# projek_robot_1_fix.net
KiCad netlist of a schematic drawn in EAGLE
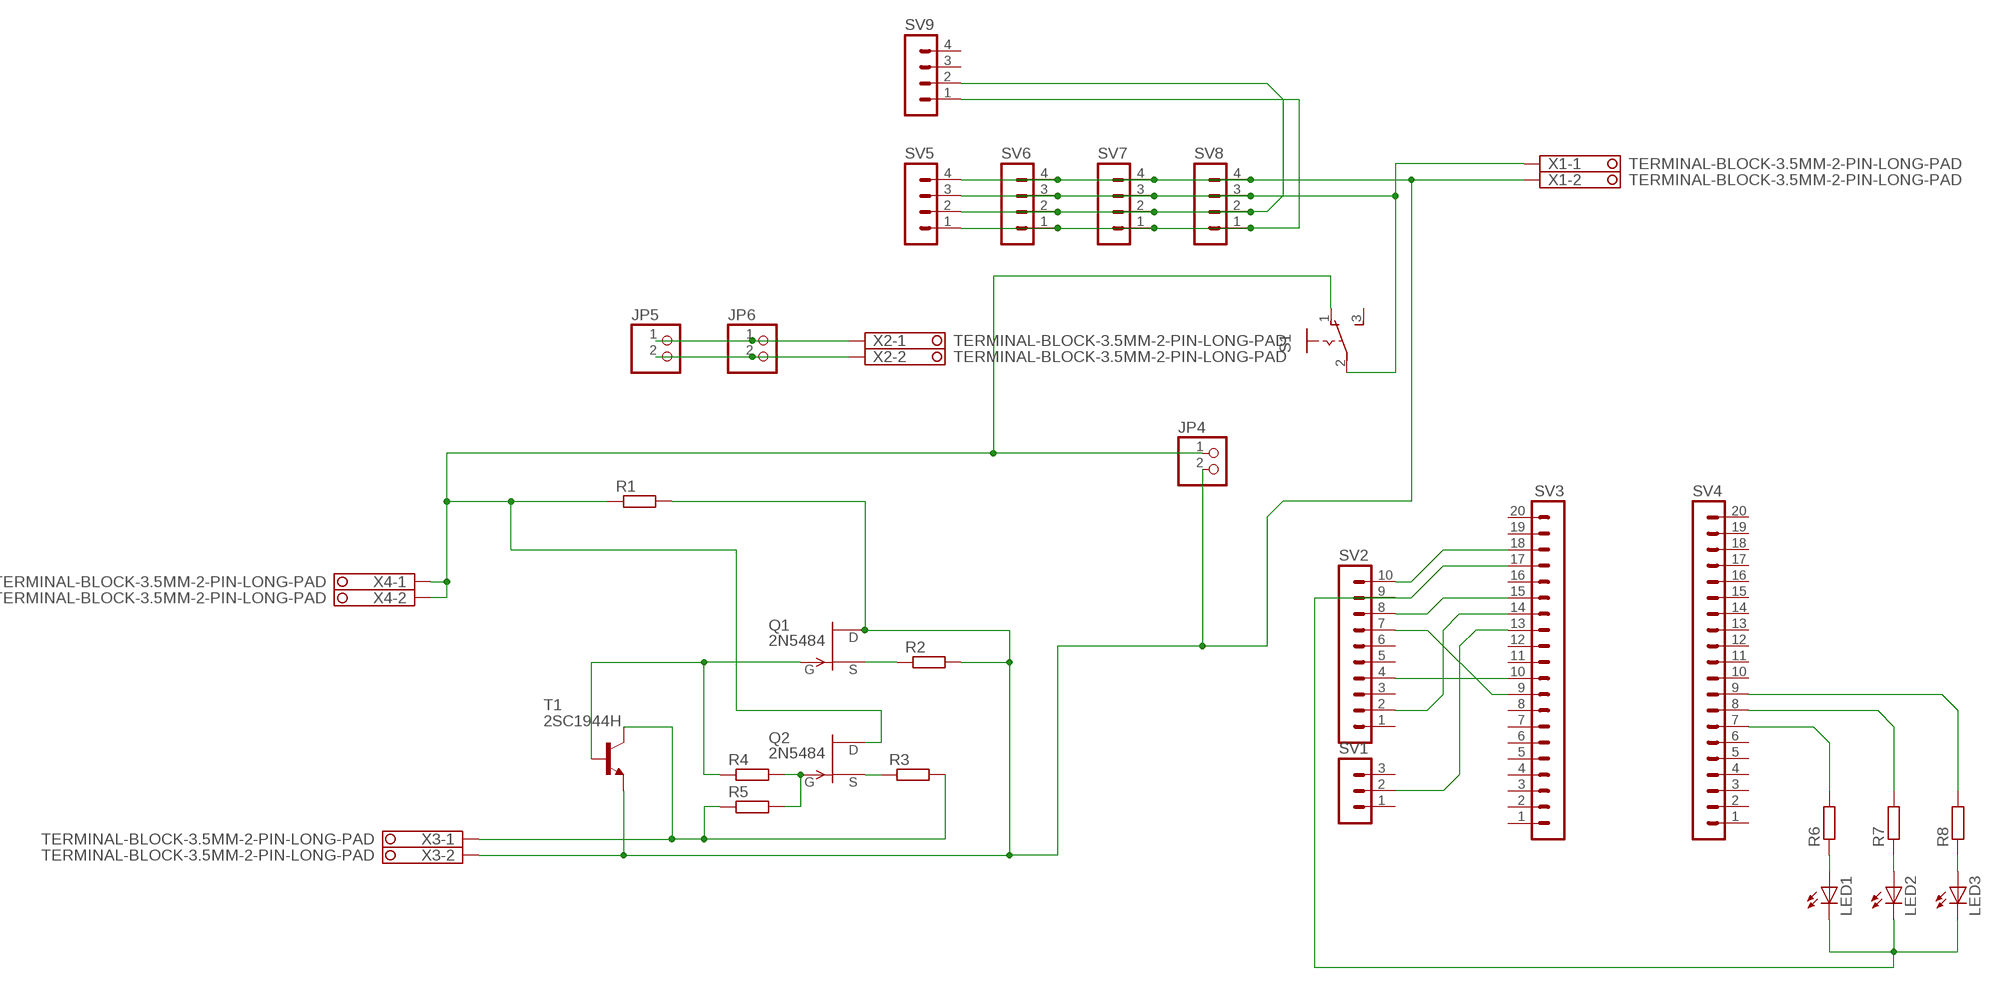
[diagram p0: schematic, sheet 1]

(export (version "E")
  (design (tool "Eeschema 10.0.6"))
  (components
    (comp (ref "JP4")
      (value "PINHD-1X2")
      (footprint "eagle-import:1X02")
      (libsource (lib "eagle-import") (part "PINHD-1X2"))
    )
    (comp (ref "JP5")
      (value "PINHD-1X2")
      (footprint "eagle-import:1X02")
      (libsource (lib "eagle-import") (part "PINHD-1X2"))
    )
    (comp (ref "JP6")
      (value "PINHD-1X2")
      (footprint "eagle-import:1X02")
      (libsource (lib "eagle-import") (part "PINHD-1X2"))
    )
    (comp (ref "LED1")
      (value "LED5MM")
      (footprint "eagle-import:LED5MM")
      (libsource (lib "eagle-import") (part "LED5MM"))
    )
    (comp (ref "LED2")
      (value "LED5MM")
      (footprint "eagle-import:LED5MM")
      (libsource (lib "eagle-import") (part "LED5MM"))
    )
    (comp (ref "LED3")
      (value "LED5MM")
      (footprint "eagle-import:LED5MM")
      (libsource (lib "eagle-import") (part "LED5MM"))
    )
    (comp (ref "Q1")
      (value "2N5484")
      (footprint "eagle-import:TO92-")
      (libsource (lib "eagle-import") (part "?5482N4"))
    )
    (comp (ref "Q2")
      (value "2N5484")
      (footprint "eagle-import:TO92-")
      (libsource (lib "eagle-import") (part "?5482N4"))
    )
    (comp (ref "R1")
      (value "R-EU_0207/7")
      (footprint "eagle-import:0207_7")
      (libsource (lib "eagle-import") (part "R-EU_0207/7"))
    )
    (comp (ref "R2")
      (value "R-EU_0207/7")
      (footprint "eagle-import:0207_7")
      (libsource (lib "eagle-import") (part "R-EU_0207/7"))
    )
    (comp (ref "R3")
      (value "R-EU_0207/7")
      (footprint "eagle-import:0207_7")
      (libsource (lib "eagle-import") (part "R-EU_0207/7"))
    )
    (comp (ref "R4")
      (value "R-EU_0207/7")
      (footprint "eagle-import:0207_7")
      (libsource (lib "eagle-import") (part "R-EU_0207/7"))
    )
    (comp (ref "R5")
      (value "R-EU_0207/7")
      (footprint "eagle-import:0207_7")
      (libsource (lib "eagle-import") (part "R-EU_0207/7"))
    )
    (comp (ref "R6")
      (value "R-EU_0207/7")
      (footprint "eagle-import:0207_7")
      (libsource (lib "eagle-import") (part "R-EU_0207/7"))
    )
    (comp (ref "R7")
      (value "R-EU_0207/7")
      (footprint "eagle-import:0207_7")
      (libsource (lib "eagle-import") (part "R-EU_0207/7"))
    )
    (comp (ref "R8")
      (value "R-EU_0207/7")
      (footprint "eagle-import:0207_7")
      (libsource (lib "eagle-import") (part "R-EU_0207/7"))
    )
    (comp (ref "S1")
      (value "M251")
      (footprint "eagle-import:M251")
      (libsource (lib "eagle-import") (part "M251"))
    )
    (comp (ref "SV1")
      (value "MA03-1")
      (footprint "eagle-import:MA03-1")
      (libsource (lib "eagle-import") (part "MA03-1"))
    )
    (comp (ref "SV2")
      (value "MA10-1")
      (footprint "eagle-import:MA10-1")
      (libsource (lib "eagle-import") (part "MA10-1"))
    )
    (comp (ref "SV3")
      (value "MA20-1")
      (footprint "eagle-import:MA20-1")
      (libsource (lib "eagle-import") (part "MA20-1"))
    )
    (comp (ref "SV4")
      (value "MA20-1")
      (footprint "eagle-import:MA20-1")
      (libsource (lib "eagle-import") (part "MA20-1"))
    )
    (comp (ref "SV5")
      (value "MA04-1")
      (footprint "eagle-import:MA04-1")
      (libsource (lib "eagle-import") (part "MA04-1"))
    )
    (comp (ref "SV6")
      (value "MA04-1")
      (footprint "eagle-import:MA04-1")
      (libsource (lib "eagle-import") (part "MA04-1"))
    )
    (comp (ref "SV7")
      (value "MA04-1")
      (footprint "eagle-import:MA04-1")
      (libsource (lib "eagle-import") (part "MA04-1"))
    )
    (comp (ref "SV8")
      (value "MA04-1")
      (footprint "eagle-import:MA04-1")
      (libsource (lib "eagle-import") (part "MA04-1"))
    )
    (comp (ref "SV9")
      (value "MA04-1")
      (footprint "eagle-import:MA04-1")
      (libsource (lib "eagle-import") (part "MA04-1"))
    )
    (comp (ref "T1")
      (value "2SC1944H")
      (footprint "eagle-import:T-30")
      (libsource (lib "eagle-import") (part "2SC1944H"))
    )
    (comp (ref "X1")
      (value "TERMINAL-BLOCK-3.5MM-2-PIN-LONG-PAD")
      (footprint "eagle-import:TERMINAL-BLOCK-2-PIN-3.5MM-LONG-PAD")
      (libsource (lib "eagle-import") (part "TERMINAL-BLOCK-3.5MM-2-PIN-LONG-PAD"))
    )
    (comp (ref "X2")
      (value "TERMINAL-BLOCK-3.5MM-2-PIN-LONG-PAD")
      (footprint "eagle-import:TERMINAL-BLOCK-2-PIN-3.5MM-LONG-PAD")
      (libsource (lib "eagle-import") (part "TERMINAL-BLOCK-3.5MM-2-PIN-LONG-PAD"))
    )
    (comp (ref "X3")
      (value "TERMINAL-BLOCK-3.5MM-2-PIN-LONG-PAD")
      (footprint "eagle-import:TERMINAL-BLOCK-2-PIN-3.5MM-LONG-PAD")
      (libsource (lib "eagle-import") (part "TERMINAL-BLOCK-3.5MM-2-PIN-LONG-PAD"))
    )
    (comp (ref "X4")
      (value "TERMINAL-BLOCK-3.5MM-2-PIN-LONG-PAD")
      (footprint "eagle-import:TERMINAL-BLOCK-2-PIN-3.5MM-LONG-PAD")
      (libsource (lib "eagle-import") (part "TERMINAL-BLOCK-3.5MM-2-PIN-LONG-PAD"))
    )
  )
  (nets
    (net (code "1") (name "Net-(LED1-C)") (class "Default")
      (node (ref "LED1") (pin "K") (pinfunction "C_K") (pintype "passive"))
      (node (ref "LED2") (pin "K") (pinfunction "C_K") (pintype "passive"))
      (node (ref "LED3") (pin "K") (pinfunction "C_K") (pintype "passive"))
      (node (ref "SV2") (pin "9") (pinfunction "9_9") (pintype "passive"))
      (node (ref "SV3") (pin "17") (pinfunction "17_17") (pintype "passive"))
    )
    (net (code "2") (name "Net-(LED1-PadA)") (class "Default")
      (node (ref "LED1") (pin "A") (pinfunction "A_A") (pintype "passive"))
      (node (ref "R6") (pin "1") (pinfunction "1_1") (pintype "passive"))
    )
    (net (code "3") (name "Net-(LED2-PadA)") (class "Default")
      (node (ref "LED2") (pin "A") (pinfunction "A_A") (pintype "passive"))
      (node (ref "R7") (pin "1") (pinfunction "1_1") (pintype "passive"))
    )
    (net (code "4") (name "Net-(LED3-PadA)") (class "Default")
      (node (ref "LED3") (pin "A") (pinfunction "A_A") (pintype "passive"))
      (node (ref "R8") (pin "1") (pinfunction "1_1") (pintype "passive"))
    )
    (net (code "5") (name "Net-(Q1-D)") (class "Default")
      (node (ref "JP4") (pin "2") (pinfunction "2_2") (pintype "passive"))
      (node (ref "Q1") (pin "3") (pinfunction "D_3") (pintype "passive"))
      (node (ref "R1") (pin "2") (pinfunction "2_2") (pintype "passive"))
      (node (ref "R2") (pin "2") (pinfunction "2_2") (pintype "passive"))
      (node (ref "SV5") (pin "4") (pinfunction "4_4") (pintype "passive"))
      (node (ref "SV6") (pin "4") (pinfunction "4_4") (pintype "passive"))
      (node (ref "SV7") (pin "4") (pinfunction "4_4") (pintype "passive"))
      (node (ref "SV8") (pin "4") (pinfunction "4_4") (pintype "passive"))
      (node (ref "T1") (pin "3") (pinfunction "E_3") (pintype "passive"))
      (node (ref "X1") (pin "2") (pinfunction "K_2") (pintype "passive"))
      (node (ref "X3") (pin "2") (pinfunction "K_2") (pintype "passive"))
    )
    (net (code "6") (name "Net-(Q1-G)") (class "Default")
      (node (ref "Q1") (pin "1") (pinfunction "G_1") (pintype "passive"))
      (node (ref "R4") (pin "1") (pinfunction "1_1") (pintype "passive"))
      (node (ref "T1") (pin "1") (pinfunction "B_1") (pintype "passive"))
    )
    (net (code "7") (name "Net-(Q1-S)") (class "Default")
      (node (ref "Q1") (pin "2") (pinfunction "S_2") (pintype "passive"))
      (node (ref "R2") (pin "1") (pinfunction "1_1") (pintype "passive"))
    )
    (net (code "8") (name "Net-(Q2-D)") (class "Default")
      (node (ref "JP4") (pin "1") (pinfunction "1_1") (pintype "passive"))
      (node (ref "Q2") (pin "3") (pinfunction "D_3") (pintype "passive"))
      (node (ref "R1") (pin "1") (pinfunction "1_1") (pintype "passive"))
      (node (ref "S1") (pin "1") (pinfunction "O_1") (pintype "passive"))
      (node (ref "X4") (pin "1") (pinfunction "K_1") (pintype "passive"))
      (node (ref "X4") (pin "2") (pinfunction "K_2") (pintype "passive"))
    )
    (net (code "9") (name "Net-(Q2-G)") (class "Default")
      (node (ref "Q2") (pin "1") (pinfunction "G_1") (pintype "passive"))
      (node (ref "R4") (pin "2") (pinfunction "2_2") (pintype "passive"))
      (node (ref "R5") (pin "2") (pinfunction "2_2") (pintype "passive"))
    )
    (net (code "10") (name "Net-(Q2-S)") (class "Default")
      (node (ref "Q2") (pin "2") (pinfunction "S_2") (pintype "passive"))
      (node (ref "R3") (pin "1") (pinfunction "1_1") (pintype "passive"))
    )
    (net (code "11") (name "Net-(R6-Pad2)") (class "Default")
      (node (ref "R6") (pin "2") (pinfunction "2_2") (pintype "passive"))
      (node (ref "SV4") (pin "7") (pinfunction "7_7") (pintype "passive"))
    )
    (net (code "12") (name "Net-(R7-Pad2)") (class "Default")
      (node (ref "R7") (pin "2") (pinfunction "2_2") (pintype "passive"))
      (node (ref "SV4") (pin "8") (pinfunction "8_8") (pintype "passive"))
    )
    (net (code "13") (name "Net-(R8-Pad2)") (class "Default")
      (node (ref "R8") (pin "2") (pinfunction "2_2") (pintype "passive"))
      (node (ref "SV4") (pin "9") (pinfunction "9_9") (pintype "passive"))
    )
    (net (code "14") (name "Net-(S1-P)") (class "Default")
      (node (ref "S1") (pin "2") (pinfunction "P_2") (pintype "passive"))
      (node (ref "SV5") (pin "3") (pinfunction "3_3") (pintype "passive"))
      (node (ref "SV6") (pin "3") (pinfunction "3_3") (pintype "passive"))
      (node (ref "SV7") (pin "3") (pinfunction "3_3") (pintype "passive"))
      (node (ref "SV8") (pin "3") (pinfunction "3_3") (pintype "passive"))
      (node (ref "X1") (pin "1") (pinfunction "K_1") (pintype "passive"))
    )
    (net (code "15") (name "Net-(SV1-Pad2)") (class "Default")
      (node (ref "SV1") (pin "2") (pinfunction "2_2") (pintype "passive"))
      (node (ref "SV3") (pin "13") (pinfunction "13_13") (pintype "passive"))
    )
    (net (code "16") (name "Net-(SV2-Pad2)") (class "Default")
      (node (ref "SV2") (pin "2") (pinfunction "2_2") (pintype "passive"))
      (node (ref "SV3") (pin "14") (pinfunction "14_14") (pintype "passive"))
    )
    (net (code "17") (name "Net-(SV2-Pad4)") (class "Default")
      (node (ref "SV2") (pin "4") (pinfunction "4_4") (pintype "passive"))
      (node (ref "SV3") (pin "10") (pinfunction "10_10") (pintype "passive"))
    )
    (net (code "18") (name "Net-(SV2-Pad7)") (class "Default")
      (node (ref "SV2") (pin "7") (pinfunction "7_7") (pintype "passive"))
      (node (ref "SV3") (pin "9") (pinfunction "9_9") (pintype "passive"))
    )
    (net (code "19") (name "Net-(SV2-Pad8)") (class "Default")
      (node (ref "SV2") (pin "8") (pinfunction "8_8") (pintype "passive"))
      (node (ref "SV3") (pin "15") (pinfunction "15_15") (pintype "passive"))
    )
    (net (code "20") (name "Net-(SV2-Pad10)") (class "Default")
      (node (ref "SV2") (pin "10") (pinfunction "10_10") (pintype "passive"))
      (node (ref "SV3") (pin "18") (pinfunction "18_18") (pintype "passive"))
    )
    (net (code "21") (name "Net-(SV5-Pad1)") (class "Default")
      (node (ref "SV5") (pin "1") (pinfunction "1_1") (pintype "passive"))
      (node (ref "SV6") (pin "1") (pinfunction "1_1") (pintype "passive"))
      (node (ref "SV7") (pin "1") (pinfunction "1_1") (pintype "passive"))
      (node (ref "SV8") (pin "1") (pinfunction "1_1") (pintype "passive"))
      (node (ref "SV9") (pin "1") (pinfunction "1_1") (pintype "passive"))
    )
    (net (code "22") (name "Net-(SV5-Pad2)") (class "Default")
      (node (ref "SV5") (pin "2") (pinfunction "2_2") (pintype "passive"))
      (node (ref "SV6") (pin "2") (pinfunction "2_2") (pintype "passive"))
      (node (ref "SV7") (pin "2") (pinfunction "2_2") (pintype "passive"))
      (node (ref "SV8") (pin "2") (pinfunction "2_2") (pintype "passive"))
      (node (ref "SV9") (pin "2") (pinfunction "2_2") (pintype "passive"))
    )
    (net (code "23") (name "Net-(T1-C)") (class "Default")
      (node (ref "R3") (pin "2") (pinfunction "2_2") (pintype "passive"))
      (node (ref "R5") (pin "1") (pinfunction "1_1") (pintype "passive"))
      (node (ref "T1") (pin "2") (pinfunction "C_2") (pintype "passive"))
      (node (ref "X3") (pin "1") (pinfunction "K_1") (pintype "passive"))
    )
    (net (code "24") (name "Net-(X2A-K)") (class "Default")
      (node (ref "JP5") (pin "1") (pinfunction "1_1") (pintype "passive"))
      (node (ref "JP6") (pin "1") (pinfunction "1_1") (pintype "passive"))
      (node (ref "X2") (pin "1") (pinfunction "K_1") (pintype "passive"))
    )
    (net (code "25") (name "Net-(X2B-K)") (class "Default")
      (node (ref "JP5") (pin "2") (pinfunction "2_2") (pintype "passive"))
      (node (ref "JP6") (pin "2") (pinfunction "2_2") (pintype "passive"))
      (node (ref "X2") (pin "2") (pinfunction "K_2") (pintype "passive"))
    )
    (net (code "26") (name "unconnected-(S1-S-Pad3)") (class "Default")
      (node (ref "S1") (pin "3") (pinfunction "S_3") (pintype "passive"))
    )
    (net (code "27") (name "unconnected-(SV1-Pad1)") (class "Default")
      (node (ref "SV1") (pin "1") (pinfunction "1_1") (pintype "passive"))
    )
    (net (code "28") (name "unconnected-(SV1-Pad3)") (class "Default")
      (node (ref "SV1") (pin "3") (pinfunction "3_3") (pintype "passive"))
    )
    (net (code "29") (name "unconnected-(SV2-Pad1)") (class "Default")
      (node (ref "SV2") (pin "1") (pinfunction "1_1") (pintype "passive"))
    )
    (net (code "30") (name "unconnected-(SV2-Pad3)") (class "Default")
      (node (ref "SV2") (pin "3") (pinfunction "3_3") (pintype "passive"))
    )
    (net (code "31") (name "unconnected-(SV2-Pad5)") (class "Default")
      (node (ref "SV2") (pin "5") (pinfunction "5_5") (pintype "passive"))
    )
    (net (code "32") (name "unconnected-(SV2-Pad6)") (class "Default")
      (node (ref "SV2") (pin "6") (pinfunction "6_6") (pintype "passive"))
    )
    (net (code "33") (name "unconnected-(SV3-Pad1)") (class "Default")
      (node (ref "SV3") (pin "1") (pinfunction "1_1") (pintype "passive"))
    )
    (net (code "34") (name "unconnected-(SV3-Pad2)") (class "Default")
      (node (ref "SV3") (pin "2") (pinfunction "2_2") (pintype "passive"))
    )
    (net (code "35") (name "unconnected-(SV3-Pad3)") (class "Default")
      (node (ref "SV3") (pin "3") (pinfunction "3_3") (pintype "passive"))
    )
    (net (code "36") (name "unconnected-(SV3-Pad4)") (class "Default")
      (node (ref "SV3") (pin "4") (pinfunction "4_4") (pintype "passive"))
    )
    (net (code "37") (name "unconnected-(SV3-Pad5)") (class "Default")
      (node (ref "SV3") (pin "5") (pinfunction "5_5") (pintype "passive"))
    )
    (net (code "38") (name "unconnected-(SV3-Pad6)") (class "Default")
      (node (ref "SV3") (pin "6") (pinfunction "6_6") (pintype "passive"))
    )
    (net (code "39") (name "unconnected-(SV3-Pad7)") (class "Default")
      (node (ref "SV3") (pin "7") (pinfunction "7_7") (pintype "passive"))
    )
    (net (code "40") (name "unconnected-(SV3-Pad8)") (class "Default")
      (node (ref "SV3") (pin "8") (pinfunction "8_8") (pintype "passive"))
    )
    (net (code "41") (name "unconnected-(SV3-Pad11)") (class "Default")
      (node (ref "SV3") (pin "11") (pinfunction "11_11") (pintype "passive"))
    )
    (net (code "42") (name "unconnected-(SV3-Pad12)") (class "Default")
      (node (ref "SV3") (pin "12") (pinfunction "12_12") (pintype "passive"))
    )
    (net (code "43") (name "unconnected-(SV3-Pad16)") (class "Default")
      (node (ref "SV3") (pin "16") (pinfunction "16_16") (pintype "passive"))
    )
    (net (code "44") (name "unconnected-(SV3-Pad19)") (class "Default")
      (node (ref "SV3") (pin "19") (pinfunction "19_19") (pintype "passive"))
    )
    (net (code "45") (name "unconnected-(SV3-Pad20)") (class "Default")
      (node (ref "SV3") (pin "20") (pinfunction "20_20") (pintype "passive"))
    )
    (net (code "46") (name "unconnected-(SV4-Pad1)") (class "Default")
      (node (ref "SV4") (pin "1") (pinfunction "1_1") (pintype "passive"))
    )
    (net (code "47") (name "unconnected-(SV4-Pad2)") (class "Default")
      (node (ref "SV4") (pin "2") (pinfunction "2_2") (pintype "passive"))
    )
    (net (code "48") (name "unconnected-(SV4-Pad3)") (class "Default")
      (node (ref "SV4") (pin "3") (pinfunction "3_3") (pintype "passive"))
    )
    (net (code "49") (name "unconnected-(SV4-Pad4)") (class "Default")
      (node (ref "SV4") (pin "4") (pinfunction "4_4") (pintype "passive"))
    )
    (net (code "50") (name "unconnected-(SV4-Pad5)") (class "Default")
      (node (ref "SV4") (pin "5") (pinfunction "5_5") (pintype "passive"))
    )
    (net (code "51") (name "unconnected-(SV4-Pad6)") (class "Default")
      (node (ref "SV4") (pin "6") (pinfunction "6_6") (pintype "passive"))
    )
    (net (code "52") (name "unconnected-(SV4-Pad10)") (class "Default")
      (node (ref "SV4") (pin "10") (pinfunction "10_10") (pintype "passive"))
    )
    (net (code "53") (name "unconnected-(SV4-Pad11)") (class "Default")
      (node (ref "SV4") (pin "11") (pinfunction "11_11") (pintype "passive"))
    )
    (net (code "54") (name "unconnected-(SV4-Pad12)") (class "Default")
      (node (ref "SV4") (pin "12") (pinfunction "12_12") (pintype "passive"))
    )
    (net (code "55") (name "unconnected-(SV4-Pad13)") (class "Default")
      (node (ref "SV4") (pin "13") (pinfunction "13_13") (pintype "passive"))
    )
    (net (code "56") (name "unconnected-(SV4-Pad14)") (class "Default")
      (node (ref "SV4") (pin "14") (pinfunction "14_14") (pintype "passive"))
    )
    (net (code "57") (name "unconnected-(SV4-Pad15)") (class "Default")
      (node (ref "SV4") (pin "15") (pinfunction "15_15") (pintype "passive"))
    )
    (net (code "58") (name "unconnected-(SV4-Pad16)") (class "Default")
      (node (ref "SV4") (pin "16") (pinfunction "16_16") (pintype "passive"))
    )
    (net (code "59") (name "unconnected-(SV4-Pad17)") (class "Default")
      (node (ref "SV4") (pin "17") (pinfunction "17_17") (pintype "passive"))
    )
    (net (code "60") (name "unconnected-(SV4-Pad18)") (class "Default")
      (node (ref "SV4") (pin "18") (pinfunction "18_18") (pintype "passive"))
    )
    (net (code "61") (name "unconnected-(SV4-Pad19)") (class "Default")
      (node (ref "SV4") (pin "19") (pinfunction "19_19") (pintype "passive"))
    )
    (net (code "62") (name "unconnected-(SV4-Pad20)") (class "Default")
      (node (ref "SV4") (pin "20") (pinfunction "20_20") (pintype "passive"))
    )
    (net (code "63") (name "unconnected-(SV9-Pad3)") (class "Default")
      (node (ref "SV9") (pin "3") (pinfunction "3_3") (pintype "passive"))
    )
    (net (code "64") (name "unconnected-(SV9-Pad4)") (class "Default")
      (node (ref "SV9") (pin "4") (pinfunction "4_4") (pintype "passive"))
    )
  )
)
